# extension_v_1_0.net
KiCad netlist of a schematic drawn in EAGLE
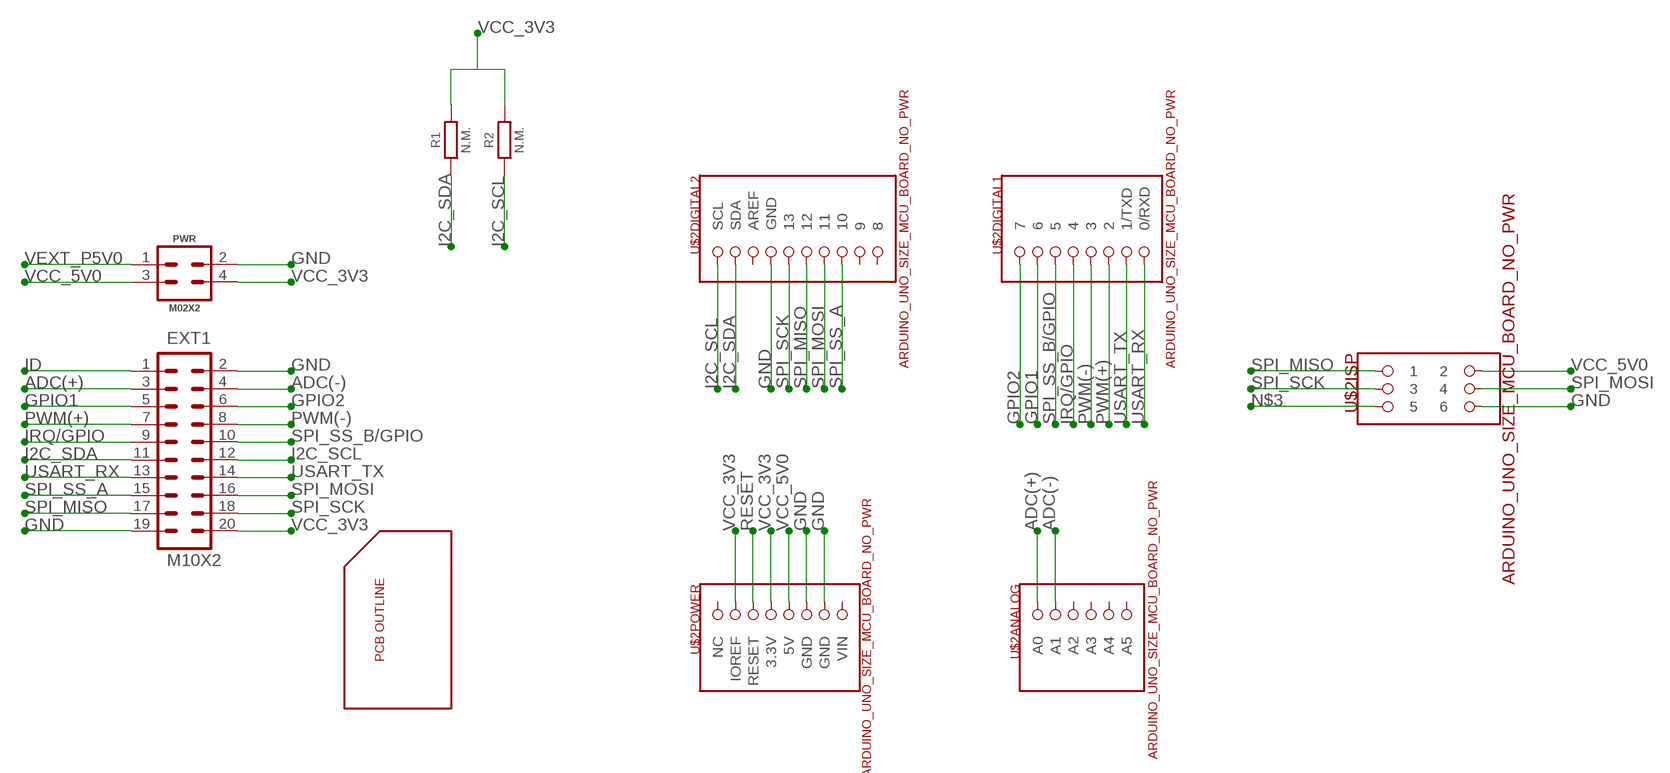
[diagram p0: schematic, sheet 1]

(export (version "E")
  (design (tool "Eeschema 10.0.6"))
  (components
    (comp (ref "EXT1")
      (value "M10X2")
      (footprint "eagle-import:2X10")
      (libsource (lib "eagle-import") (part "M10X2"))
    )
    (comp (ref "PWR")
      (value "M02X2")
      (footprint "eagle-import:H4X2_100_MIL")
      (libsource (lib "eagle-import") (part "M02X2"))
    )
    (comp (ref "R1")
      (value "N.M.")
      (footprint "eagle-import:0603")
      (libsource (lib "eagle-import") (part "R0603"))
    )
    (comp (ref "R2")
      (value "N.M.")
      (footprint "eagle-import:0603")
      (libsource (lib "eagle-import") (part "R0603"))
    )
    (comp (ref "U$2")
      (value "ARDUINO_UNO_SIZE_MCU_BOARD_NO_PWR")
      (footprint "eagle-import:STANDARD_NO_PWR")
      (libsource (lib "eagle-import") (part "ARDUINO_UNO_SIZE_MCU_BOARD_NO_PWR"))
    )
  )
  (nets
    (net (code "1") (name "/ADC(+)") (class "Default")
      (node (ref "EXT1") (pin "3") (pinfunction "3_3") (pintype "passive"))
      (node (ref "U$2") (pin "9") (pinfunction "A0_9") (pintype "bidirectional"))
    )
    (net (code "2") (name "/ADC(-)") (class "Default")
      (node (ref "EXT1") (pin "4") (pinfunction "4_4") (pintype "passive"))
      (node (ref "U$2") (pin "11") (pinfunction "A1_11") (pintype "bidirectional"))
    )
    (net (code "3") (name "/GND") (class "Default")
      (node (ref "EXT1") (pin "19") (pinfunction "19_19") (pintype "passive"))
      (node (ref "EXT1") (pin "2") (pinfunction "2_2") (pintype "passive"))
      (node (ref "PWR") (pin "2") (pinfunction "2_2") (pintype "bidirectional"))
      (node (ref "U$2") (pin "30") (pinfunction "GND_30") (pintype "bidirectional"))
      (node (ref "U$2") (pin "6") (pinfunction "GND_6") (pintype "bidirectional"))
      (node (ref "U$2") (pin "7") (pinfunction "GND_7") (pintype "bidirectional"))
      (node (ref "U$2") (pin "ISCP6") (pinfunction "6_ISCP6") (pintype "bidirectional"))
    )
    (net (code "4") (name "/GPIO1") (class "Default")
      (node (ref "EXT1") (pin "5") (pinfunction "5_5") (pintype "passive"))
      (node (ref "U$2") (pin "22") (pinfunction "6_22") (pintype "bidirectional"))
    )
    (net (code "5") (name "/GPIO2") (class "Default")
      (node (ref "EXT1") (pin "6") (pinfunction "6_6") (pintype "passive"))
      (node (ref "U$2") (pin "23") (pinfunction "7_23") (pintype "bidirectional"))
    )
    (net (code "6") (name "/I2C_SCL") (class "Default")
      (node (ref "EXT1") (pin "12") (pinfunction "12_12") (pintype "passive"))
      (node (ref "R2") (pin "1") (pinfunction "1_1") (pintype "passive"))
      (node (ref "U$2") (pin "50") (pinfunction "SCL_50") (pintype "bidirectional"))
    )
    (net (code "7") (name "/I2C_SDA") (class "Default")
      (node (ref "EXT1") (pin "11") (pinfunction "11_11") (pintype "passive"))
      (node (ref "R1") (pin "1") (pinfunction "1_1") (pintype "passive"))
      (node (ref "U$2") (pin "60") (pinfunction "SDA_60") (pintype "bidirectional"))
    )
    (net (code "8") (name "/ID") (class "Default")
      (node (ref "EXT1") (pin "1") (pinfunction "1_1") (pintype "passive"))
    )
    (net (code "9") (name "/IRQ{slash}GPIO") (class "Default")
      (node (ref "EXT1") (pin "9") (pinfunction "9_9") (pintype "passive"))
      (node (ref "U$2") (pin "20") (pinfunction "4_20") (pintype "bidirectional"))
    )
    (net (code "10") (name "/N$3") (class "Default")
      (node (ref "U$2") (pin "ISCP5") (pinfunction "5_ISCP5") (pintype "bidirectional"))
    )
    (net (code "11") (name "/PWM(+)") (class "Default")
      (node (ref "EXT1") (pin "7") (pinfunction "7_7") (pintype "passive"))
      (node (ref "U$2") (pin "18") (pinfunction "2_18") (pintype "bidirectional"))
    )
    (net (code "12") (name "/PWM(-)") (class "Default")
      (node (ref "EXT1") (pin "8") (pinfunction "8_8") (pintype "passive"))
      (node (ref "U$2") (pin "19") (pinfunction "3_19") (pintype "bidirectional"))
    )
    (net (code "13") (name "/RESET") (class "Default")
      (node (ref "U$2") (pin "3") (pinfunction "RESET_3") (pintype "bidirectional"))
    )
    (net (code "14") (name "/SPI_MISO") (class "Default")
      (node (ref "EXT1") (pin "17") (pinfunction "17_17") (pintype "passive"))
      (node (ref "U$2") (pin "28") (pinfunction "12_28") (pintype "bidirectional"))
      (node (ref "U$2") (pin "ICSP1") (pinfunction "1_ICSP1") (pintype "bidirectional"))
    )
    (net (code "15") (name "/SPI_MOSI") (class "Default")
      (node (ref "EXT1") (pin "16") (pinfunction "16_16") (pintype "passive"))
      (node (ref "U$2") (pin "27") (pinfunction "11_27") (pintype "bidirectional"))
      (node (ref "U$2") (pin "ISCP4") (pinfunction "4_ISCP4") (pintype "bidirectional"))
    )
    (net (code "16") (name "/SPI_SCK") (class "Default")
      (node (ref "EXT1") (pin "18") (pinfunction "18_18") (pintype "passive"))
      (node (ref "U$2") (pin "29") (pinfunction "13_29") (pintype "bidirectional"))
      (node (ref "U$2") (pin "ISCP3") (pinfunction "3_ISCP3") (pintype "bidirectional"))
    )
    (net (code "17") (name "/SPI_SS_A") (class "Default")
      (node (ref "EXT1") (pin "15") (pinfunction "15_15") (pintype "passive"))
      (node (ref "U$2") (pin "26") (pinfunction "10_26") (pintype "bidirectional"))
    )
    (net (code "18") (name "/SPI_SS_B{slash}GPIO") (class "Default")
      (node (ref "EXT1") (pin "10") (pinfunction "10_10") (pintype "passive"))
      (node (ref "U$2") (pin "21") (pinfunction "5_21") (pintype "bidirectional"))
    )
    (net (code "19") (name "/USART_RX") (class "Default")
      (node (ref "EXT1") (pin "13") (pinfunction "13_13") (pintype "passive"))
      (node (ref "U$2") (pin "16") (pinfunction "0/RXD_16") (pintype "bidirectional"))
    )
    (net (code "20") (name "/USART_TX") (class "Default")
      (node (ref "EXT1") (pin "14") (pinfunction "14_14") (pintype "passive"))
      (node (ref "U$2") (pin "17") (pinfunction "1/TXD_17") (pintype "bidirectional"))
    )
    (net (code "21") (name "/VCC_3V3") (class "Default")
      (node (ref "EXT1") (pin "20") (pinfunction "20_20") (pintype "passive"))
      (node (ref "PWR") (pin "4") (pinfunction "4_4") (pintype "bidirectional"))
      (node (ref "R1") (pin "2") (pinfunction "2_2") (pintype "passive"))
      (node (ref "R2") (pin "2") (pinfunction "2_2") (pintype "passive"))
      (node (ref "U$2") (pin "2") (pinfunction "IOREF_2") (pintype "bidirectional"))
      (node (ref "U$2") (pin "4") (pinfunction "3.3V_4") (pintype "bidirectional"))
    )
    (net (code "22") (name "/VCC_5V0") (class "Default")
      (node (ref "PWR") (pin "3") (pinfunction "3_3") (pintype "bidirectional"))
      (node (ref "U$2") (pin "5") (pinfunction "5V_5") (pintype "bidirectional"))
      (node (ref "U$2") (pin "ICSP2") (pinfunction "2_ICSP2") (pintype "bidirectional"))
    )
    (net (code "23") (name "/VEXT_P5V0") (class "Default")
      (node (ref "PWR") (pin "1") (pinfunction "1_1") (pintype "bidirectional"))
    )
    (net (code "24") (name "unconnected-(U$2A-A2-Pad12)") (class "Default")
      (node (ref "U$2") (pin "12") (pinfunction "A2_12") (pintype "bidirectional"))
    )
    (net (code "25") (name "unconnected-(U$2A-A3-Pad13)") (class "Default")
      (node (ref "U$2") (pin "13") (pinfunction "A3_13") (pintype "bidirectional"))
    )
    (net (code "26") (name "unconnected-(U$2A-A4-Pad14)") (class "Default")
      (node (ref "U$2") (pin "14") (pinfunction "A4_14") (pintype "bidirectional"))
    )
    (net (code "27") (name "unconnected-(U$2A-A5-Pad15)") (class "Default")
      (node (ref "U$2") (pin "15") (pinfunction "A5_15") (pintype "bidirectional"))
    )
    (net (code "28") (name "unconnected-(U$2C-8-Pad24)") (class "Default")
      (node (ref "U$2") (pin "24") (pinfunction "8_24") (pintype "bidirectional"))
    )
    (net (code "29") (name "unconnected-(U$2C-9-Pad25)") (class "Default")
      (node (ref "U$2") (pin "25") (pinfunction "9_25") (pintype "bidirectional"))
    )
    (net (code "30") (name "unconnected-(U$2C-AREF-Pad40)") (class "Default")
      (node (ref "U$2") (pin "40") (pinfunction "AREF_40") (pintype "bidirectional"))
    )
    (net (code "31") (name "unconnected-(U$2F-NC-Pad1)") (class "Default")
      (node (ref "U$2") (pin "1") (pinfunction "NC_1") (pintype "bidirectional"))
    )
    (net (code "32") (name "unconnected-(U$2F-VIN-Pad8)") (class "Default")
      (node (ref "U$2") (pin "8") (pinfunction "VIN_8") (pintype "bidirectional"))
    )
  )
)
